# indicator-4x3-chain-v1.net
KiCad netlist of a schematic drawn in EAGLE
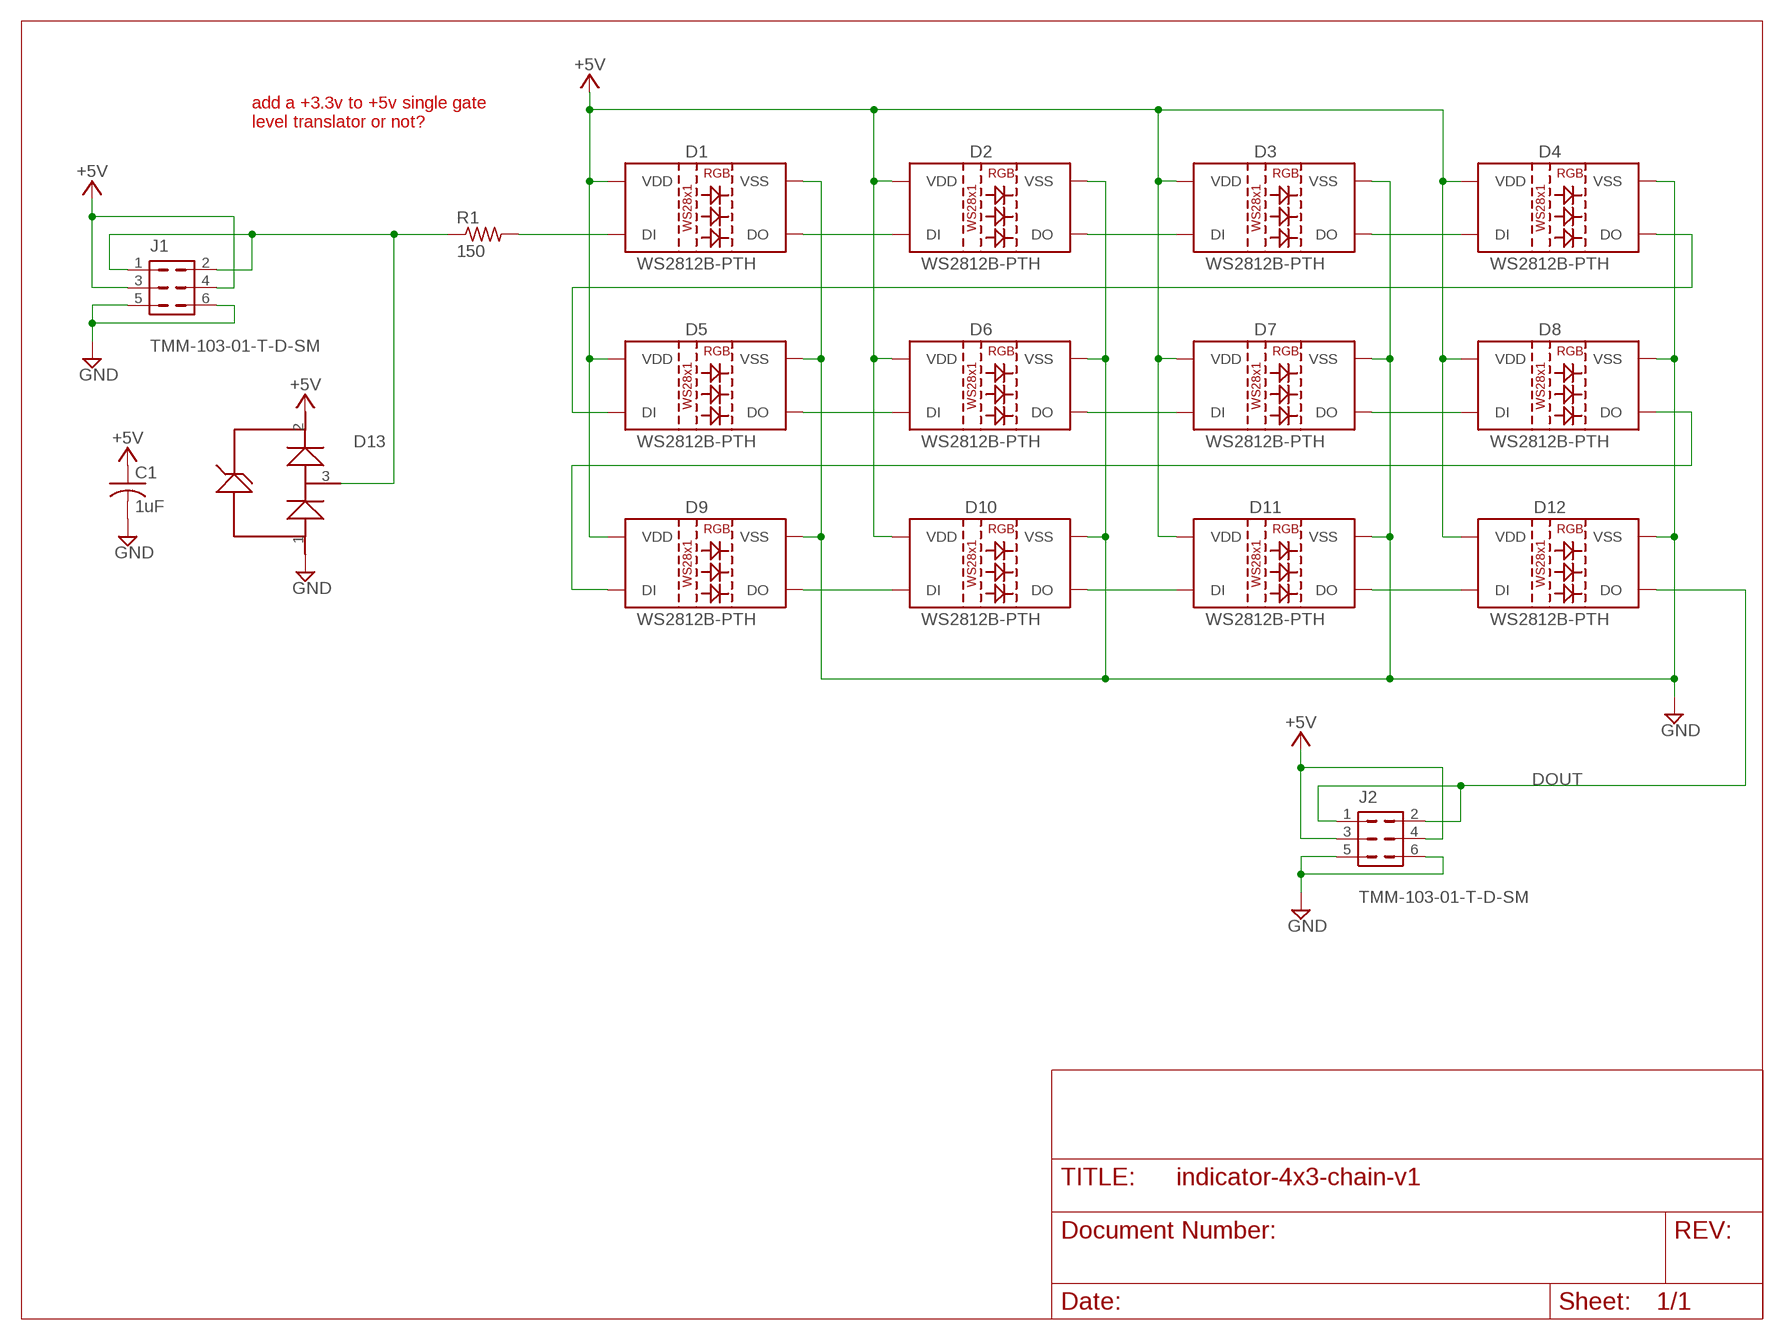
[diagram p0: schematic, sheet 1]

(export (version "E")
  (design (tool "Eeschema 10.0.6"))
  (components
    (comp (ref "C1")
      (value "1uF")
      (footprint "eagle-import:C0603K")
      (libsource (lib "eagle-import") (part "C-USC0603K"))
    )
    (comp (ref "D1")
      (value "WS2812B-PTH")
      (footprint "eagle-import:WS2812B-PTH-KIT")
      (libsource (lib "eagle-import") (part "WS2812B-PTH"))
    )
    (comp (ref "D2")
      (value "WS2812B-PTH")
      (footprint "eagle-import:WS2812B-PTH-KIT")
      (libsource (lib "eagle-import") (part "WS2812B-PTH"))
    )
    (comp (ref "D3")
      (value "WS2812B-PTH")
      (footprint "eagle-import:WS2812B-PTH-KIT")
      (libsource (lib "eagle-import") (part "WS2812B-PTH"))
    )
    (comp (ref "D4")
      (value "WS2812B-PTH")
      (footprint "eagle-import:WS2812B-PTH-KIT")
      (libsource (lib "eagle-import") (part "WS2812B-PTH"))
    )
    (comp (ref "D5")
      (value "WS2812B-PTH")
      (footprint "eagle-import:WS2812B-PTH-KIT")
      (libsource (lib "eagle-import") (part "WS2812B-PTH"))
    )
    (comp (ref "D6")
      (value "WS2812B-PTH")
      (footprint "eagle-import:WS2812B-PTH-KIT")
      (libsource (lib "eagle-import") (part "WS2812B-PTH"))
    )
    (comp (ref "D7")
      (value "WS2812B-PTH")
      (footprint "eagle-import:WS2812B-PTH-KIT")
      (libsource (lib "eagle-import") (part "WS2812B-PTH"))
    )
    (comp (ref "D8")
      (value "WS2812B-PTH")
      (footprint "eagle-import:WS2812B-PTH-KIT")
      (libsource (lib "eagle-import") (part "WS2812B-PTH"))
    )
    (comp (ref "D9")
      (value "WS2812B-PTH")
      (footprint "eagle-import:WS2812B-PTH-KIT")
      (libsource (lib "eagle-import") (part "WS2812B-PTH"))
    )
    (comp (ref "D10")
      (value "WS2812B-PTH")
      (footprint "eagle-import:WS2812B-PTH-KIT")
      (libsource (lib "eagle-import") (part "WS2812B-PTH"))
    )
    (comp (ref "D11")
      (value "WS2812B-PTH")
      (footprint "eagle-import:WS2812B-PTH-KIT")
      (libsource (lib "eagle-import") (part "WS2812B-PTH"))
    )
    (comp (ref "D12")
      (value "WS2812B-PTH")
      (footprint "eagle-import:WS2812B-PTH-KIT")
      (libsource (lib "eagle-import") (part "WS2812B-PTH"))
    )
    (comp (ref "D13")
      (value "DRTR5V0U1SO")
      (footprint "eagle-import:SOT23-3")
      (fields (field (name "MFR") "DIODES INC") (field (name "MFR_PART_NO") "DRTR5V0U1SO"))
      (libsource (lib "eagle-import") (part "DRTR5V0U1SO"))
    )
    (comp (ref "J1")
      (value "TMM-103-01-T-D-SM")
      (footprint "eagle-import:2MM-SMD-HEADER-2X3")
      (libsource (lib "eagle-import") (part "TMM-103-01-T-D-SM"))
    )
    (comp (ref "J2")
      (value "TMM-103-01-T-D-SM")
      (footprint "eagle-import:2MM-SMD-HEADER-2X3")
      (libsource (lib "eagle-import") (part "TMM-103-01-T-D-SM"))
    )
    (comp (ref "R1")
      (value "150")
      (footprint "eagle-import:R0603")
      (libsource (lib "eagle-import") (part "R-US_R0603"))
    )
  )
  (nets
    (net (code "1") (name "+5V") (class "Default")
      (node (ref "C1") (pin "1") (pinfunction "1_1") (pintype "passive"))
      (node (ref "D1") (pin "2") (pinfunction "VDD_2") (pintype "bidirectional"))
      (node (ref "D10") (pin "2") (pinfunction "VDD_2") (pintype "bidirectional"))
      (node (ref "D11") (pin "2") (pinfunction "VDD_2") (pintype "bidirectional"))
      (node (ref "D12") (pin "2") (pinfunction "VDD_2") (pintype "bidirectional"))
      (node (ref "D13") (pin "2") (pinfunction "2_2") (pintype "bidirectional"))
      (node (ref "D2") (pin "2") (pinfunction "VDD_2") (pintype "bidirectional"))
      (node (ref "D3") (pin "2") (pinfunction "VDD_2") (pintype "bidirectional"))
      (node (ref "D4") (pin "2") (pinfunction "VDD_2") (pintype "bidirectional"))
      (node (ref "D5") (pin "2") (pinfunction "VDD_2") (pintype "bidirectional"))
      (node (ref "D6") (pin "2") (pinfunction "VDD_2") (pintype "bidirectional"))
      (node (ref "D7") (pin "2") (pinfunction "VDD_2") (pintype "bidirectional"))
      (node (ref "D8") (pin "2") (pinfunction "VDD_2") (pintype "bidirectional"))
      (node (ref "D9") (pin "2") (pinfunction "VDD_2") (pintype "bidirectional"))
      (node (ref "J1") (pin "3") (pinfunction "3_3") (pintype "passive"))
      (node (ref "J1") (pin "4") (pinfunction "4_4") (pintype "passive"))
      (node (ref "J2") (pin "3") (pinfunction "3_3") (pintype "passive"))
      (node (ref "J2") (pin "4") (pinfunction "4_4") (pintype "passive"))
    )
    (net (code "2") (name "/DOUT") (class "Default")
      (node (ref "D12") (pin "4") (pinfunction "DO_4") (pintype "bidirectional"))
      (node (ref "J2") (pin "1") (pinfunction "1_1") (pintype "passive"))
      (node (ref "J2") (pin "2") (pinfunction "2_2") (pintype "passive"))
    )
    (net (code "3") (name "GND") (class "Default")
      (node (ref "C1") (pin "2") (pinfunction "2_2") (pintype "passive"))
      (node (ref "D1") (pin "3") (pinfunction "VSS_3") (pintype "bidirectional"))
      (node (ref "D10") (pin "3") (pinfunction "VSS_3") (pintype "bidirectional"))
      (node (ref "D11") (pin "3") (pinfunction "VSS_3") (pintype "bidirectional"))
      (node (ref "D12") (pin "3") (pinfunction "VSS_3") (pintype "bidirectional"))
      (node (ref "D13") (pin "1") (pinfunction "3_1") (pintype "bidirectional"))
      (node (ref "D2") (pin "3") (pinfunction "VSS_3") (pintype "bidirectional"))
      (node (ref "D3") (pin "3") (pinfunction "VSS_3") (pintype "bidirectional"))
      (node (ref "D4") (pin "3") (pinfunction "VSS_3") (pintype "bidirectional"))
      (node (ref "D5") (pin "3") (pinfunction "VSS_3") (pintype "bidirectional"))
      (node (ref "D6") (pin "3") (pinfunction "VSS_3") (pintype "bidirectional"))
      (node (ref "D7") (pin "3") (pinfunction "VSS_3") (pintype "bidirectional"))
      (node (ref "D8") (pin "3") (pinfunction "VSS_3") (pintype "bidirectional"))
      (node (ref "D9") (pin "3") (pinfunction "VSS_3") (pintype "bidirectional"))
      (node (ref "J1") (pin "5") (pinfunction "5_5") (pintype "passive"))
      (node (ref "J1") (pin "6") (pinfunction "6_6") (pintype "passive"))
      (node (ref "J2") (pin "5") (pinfunction "5_5") (pintype "passive"))
      (node (ref "J2") (pin "6") (pinfunction "6_6") (pintype "passive"))
    )
    (net (code "4") (name "Net-(D1-DI)") (class "Default")
      (node (ref "D1") (pin "1") (pinfunction "DI_1") (pintype "bidirectional"))
      (node (ref "R1") (pin "2") (pinfunction "2_2") (pintype "passive"))
    )
    (net (code "5") (name "Net-(D1-DO)") (class "Default")
      (node (ref "D1") (pin "4") (pinfunction "DO_4") (pintype "bidirectional"))
      (node (ref "D2") (pin "1") (pinfunction "DI_1") (pintype "bidirectional"))
    )
    (net (code "6") (name "Net-(D2-DO)") (class "Default")
      (node (ref "D2") (pin "4") (pinfunction "DO_4") (pintype "bidirectional"))
      (node (ref "D3") (pin "1") (pinfunction "DI_1") (pintype "bidirectional"))
    )
    (net (code "7") (name "Net-(D3-DO)") (class "Default")
      (node (ref "D3") (pin "4") (pinfunction "DO_4") (pintype "bidirectional"))
      (node (ref "D4") (pin "1") (pinfunction "DI_1") (pintype "bidirectional"))
    )
    (net (code "8") (name "Net-(D4-DO)") (class "Default")
      (node (ref "D4") (pin "4") (pinfunction "DO_4") (pintype "bidirectional"))
      (node (ref "D5") (pin "1") (pinfunction "DI_1") (pintype "bidirectional"))
    )
    (net (code "9") (name "Net-(D5-DO)") (class "Default")
      (node (ref "D5") (pin "4") (pinfunction "DO_4") (pintype "bidirectional"))
      (node (ref "D6") (pin "1") (pinfunction "DI_1") (pintype "bidirectional"))
    )
    (net (code "10") (name "Net-(D6-DO)") (class "Default")
      (node (ref "D6") (pin "4") (pinfunction "DO_4") (pintype "bidirectional"))
      (node (ref "D7") (pin "1") (pinfunction "DI_1") (pintype "bidirectional"))
    )
    (net (code "11") (name "Net-(D7-DO)") (class "Default")
      (node (ref "D7") (pin "4") (pinfunction "DO_4") (pintype "bidirectional"))
      (node (ref "D8") (pin "1") (pinfunction "DI_1") (pintype "bidirectional"))
    )
    (net (code "12") (name "Net-(D8-DO)") (class "Default")
      (node (ref "D8") (pin "4") (pinfunction "DO_4") (pintype "bidirectional"))
      (node (ref "D9") (pin "1") (pinfunction "DI_1") (pintype "bidirectional"))
    )
    (net (code "13") (name "Net-(D10-DI)") (class "Default")
      (node (ref "D10") (pin "1") (pinfunction "DI_1") (pintype "bidirectional"))
      (node (ref "D9") (pin "4") (pinfunction "DO_4") (pintype "bidirectional"))
    )
    (net (code "14") (name "Net-(D10-DO)") (class "Default")
      (node (ref "D10") (pin "4") (pinfunction "DO_4") (pintype "bidirectional"))
      (node (ref "D11") (pin "1") (pinfunction "DI_1") (pintype "bidirectional"))
    )
    (net (code "15") (name "Net-(D11-DO)") (class "Default")
      (node (ref "D11") (pin "4") (pinfunction "DO_4") (pintype "bidirectional"))
      (node (ref "D12") (pin "1") (pinfunction "DI_1") (pintype "bidirectional"))
    )
    (net (code "16") (name "Net-(D13-1)") (class "Default")
      (node (ref "D13") (pin "3") (pinfunction "1_3") (pintype "bidirectional"))
      (node (ref "J1") (pin "1") (pinfunction "1_1") (pintype "passive"))
      (node (ref "J1") (pin "2") (pinfunction "2_2") (pintype "passive"))
      (node (ref "R1") (pin "1") (pinfunction "1_1") (pintype "passive"))
    )
  )
)
